# NintendoNinjaSchematic.net
KiCad netlist of a schematic drawn in EAGLE
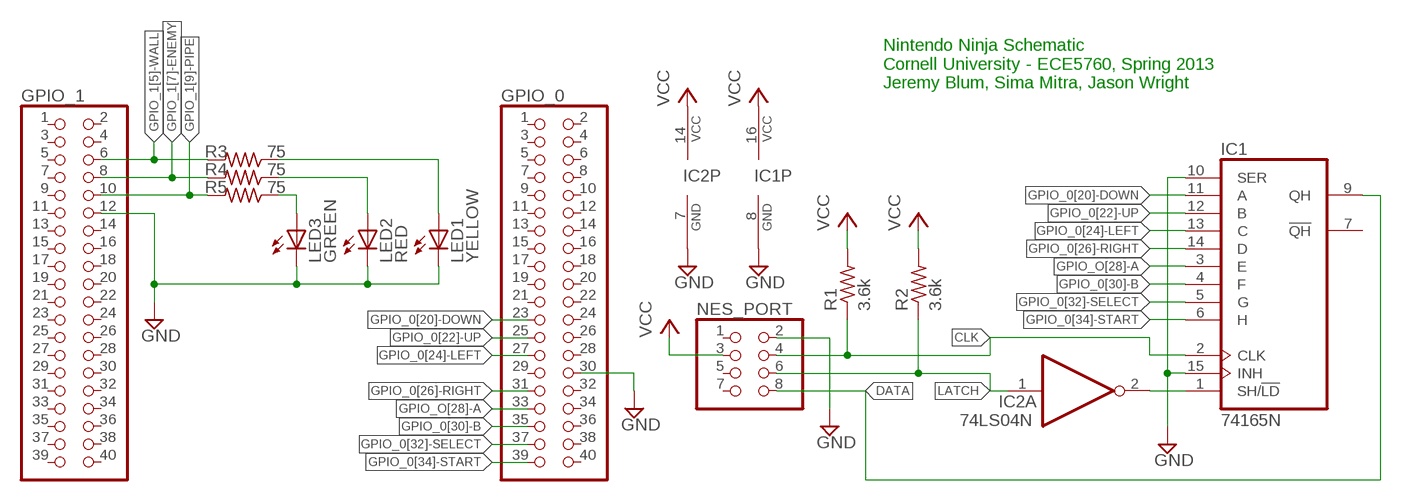
[diagram p0: schematic, sheet 1]

(export (version "E")
  (design (tool "Eeschema 10.0.6"))
  (components
    (comp (ref "GPIO_0")
      (value "PINHD-2X20")
      (footprint "eagle-import:2X20")
      (libsource (lib "eagle-import") (part "PINHD-2X20"))
    )
    (comp (ref "GPIO_1")
      (value "PINHD-2X20")
      (footprint "eagle-import:2X20")
      (libsource (lib "eagle-import") (part "PINHD-2X20"))
    )
    (comp (ref "IC1")
      (value "74165N")
      (footprint "eagle-import:DIL16")
      (libsource (lib "eagle-import") (part "74165N"))
    )
    (comp (ref "IC2")
      (value "74LS04N")
      (footprint "eagle-import:DIL14")
      (libsource (lib "eagle-import") (part "7404NLS"))
    )
    (comp (ref "LED1")
      (value "YELLOW")
      (footprint "eagle-import:LED5MM")
      (libsource (lib "eagle-import") (part "LED5MM"))
    )
    (comp (ref "LED2")
      (value "RED")
      (footprint "eagle-import:LED5MM")
      (libsource (lib "eagle-import") (part "LED5MM"))
    )
    (comp (ref "LED3")
      (value "GREEN")
      (footprint "eagle-import:LED5MM")
      (libsource (lib "eagle-import") (part "LED5MM"))
    )
    (comp (ref "NES_PORT")
      (value "PINHD-2X4")
      (footprint "eagle-import:2X04")
      (libsource (lib "eagle-import") (part "PINHD-2X4"))
    )
    (comp (ref "R1")
      (value "3.6k")
      (footprint "eagle-import:V526-0")
      (libsource (lib "eagle-import") (part "R-US_V526-0"))
    )
    (comp (ref "R2")
      (value "3.6k")
      (footprint "eagle-import:V526-0")
      (libsource (lib "eagle-import") (part "R-US_V526-0"))
    )
    (comp (ref "R3")
      (value "75")
      (footprint "eagle-import:V526-0")
      (libsource (lib "eagle-import") (part "R-US_V526-0"))
    )
    (comp (ref "R4")
      (value "75")
      (footprint "eagle-import:V526-0")
      (libsource (lib "eagle-import") (part "R-US_V526-0"))
    )
    (comp (ref "R5")
      (value "75")
      (footprint "eagle-import:V526-0")
      (libsource (lib "eagle-import") (part "R-US_V526-0"))
    )
  )
  (nets
    (net (code "1") (name "CLK") (class "Default")
      (node (ref "IC1") (pin "2") (pinfunction "CLK_2") (pintype "input"))
      (node (ref "NES_PORT") (pin "4") (pinfunction "4_4") (pintype "passive"))
      (node (ref "R1") (pin "1") (pinfunction "1_1") (pintype "passive"))
    )
    (net (code "2") (name "DATA") (class "Default")
      (node (ref "IC1") (pin "9") (pinfunction "QH_9") (pintype "output"))
      (node (ref "NES_PORT") (pin "8") (pinfunction "8_8") (pintype "passive"))
    )
    (net (code "3") (name "GND") (class "Default")
      (node (ref "GPIO_0") (pin "30") (pinfunction "30_30") (pintype "passive"))
      (node (ref "GPIO_1") (pin "12") (pinfunction "12_12") (pintype "passive"))
      (node (ref "IC1") (pin "10") (pinfunction "SER_10") (pintype "input"))
      (node (ref "IC1") (pin "15") (pinfunction "INH_15") (pintype "input"))
      (node (ref "IC1") (pin "8") (pinfunction "GND_8") (pintype "power_in"))
      (node (ref "IC2") (pin "7") (pinfunction "GND_7") (pintype "power_in"))
      (node (ref "LED1") (pin "K") (pinfunction "C_K") (pintype "passive"))
      (node (ref "LED2") (pin "K") (pinfunction "C_K") (pintype "passive"))
      (node (ref "LED3") (pin "K") (pinfunction "C_K") (pintype "passive"))
      (node (ref "NES_PORT") (pin "2") (pinfunction "2_2") (pintype "passive"))
    )
    (net (code "4") (name "GPIO_0[20]-DOWN") (class "Default")
      (node (ref "GPIO_0") (pin "23") (pinfunction "23_23") (pintype "passive"))
      (node (ref "IC1") (pin "11") (pinfunction "A_11") (pintype "input"))
    )
    (net (code "5") (name "GPIO_0[22]-UP") (class "Default")
      (node (ref "GPIO_0") (pin "25") (pinfunction "25_25") (pintype "passive"))
      (node (ref "IC1") (pin "12") (pinfunction "B_12") (pintype "input"))
    )
    (net (code "6") (name "GPIO_0[24]-LEFT") (class "Default")
      (node (ref "GPIO_0") (pin "27") (pinfunction "27_27") (pintype "passive"))
      (node (ref "IC1") (pin "13") (pinfunction "C_13") (pintype "input"))
    )
    (net (code "7") (name "GPIO_0[26]-RIGHT") (class "Default")
      (node (ref "GPIO_0") (pin "31") (pinfunction "31_31") (pintype "passive"))
      (node (ref "IC1") (pin "14") (pinfunction "D_14") (pintype "input"))
    )
    (net (code "8") (name "GPIO_0[30]-B") (class "Default")
      (node (ref "GPIO_0") (pin "35") (pinfunction "35_35") (pintype "passive"))
      (node (ref "IC1") (pin "4") (pinfunction "F_4") (pintype "input"))
    )
    (net (code "9") (name "GPIO_0[32]-SELECT") (class "Default")
      (node (ref "GPIO_0") (pin "37") (pinfunction "37_37") (pintype "passive"))
      (node (ref "IC1") (pin "5") (pinfunction "G_5") (pintype "input"))
    )
    (net (code "10") (name "GPIO_0[34]-START") (class "Default")
      (node (ref "GPIO_0") (pin "39") (pinfunction "39_39") (pintype "passive"))
      (node (ref "IC1") (pin "6") (pinfunction "H_6") (pintype "input"))
    )
    (net (code "11") (name "GPIO_1[5]-WALL") (class "Default")
      (node (ref "GPIO_1") (pin "6") (pinfunction "6_6") (pintype "passive"))
      (node (ref "R3") (pin "2") (pinfunction "2_2") (pintype "passive"))
    )
    (net (code "12") (name "GPIO_1[7]-ENEMY") (class "Default")
      (node (ref "GPIO_1") (pin "8") (pinfunction "8_8") (pintype "passive"))
      (node (ref "R4") (pin "2") (pinfunction "2_2") (pintype "passive"))
    )
    (net (code "13") (name "GPIO_1[9]-PIPE") (class "Default")
      (node (ref "GPIO_1") (pin "10") (pinfunction "10_10") (pintype "passive"))
      (node (ref "R5") (pin "2") (pinfunction "2_2") (pintype "passive"))
    )
    (net (code "14") (name "GPIO_O[28]-A") (class "Default")
      (node (ref "GPIO_0") (pin "33") (pinfunction "33_33") (pintype "passive"))
      (node (ref "IC1") (pin "3") (pinfunction "E_3") (pintype "input"))
    )
    (net (code "15") (name "LATCH") (class "Default")
      (node (ref "IC2") (pin "1") (pinfunction "I_1") (pintype "input"))
      (node (ref "NES_PORT") (pin "6") (pinfunction "6_6") (pintype "passive"))
      (node (ref "R2") (pin "1") (pinfunction "1_1") (pintype "passive"))
    )
    (net (code "16") (name "Net-(IC1A-SH{slash}~{LD})") (class "Default")
      (node (ref "IC1") (pin "1") (pinfunction "SH/~{LD}_1") (pintype "input"))
      (node (ref "IC2") (pin "2") (pinfunction "O_2") (pintype "output"))
    )
    (net (code "17") (name "Net-(LED1-PadA)") (class "Default")
      (node (ref "LED1") (pin "A") (pinfunction "A_A") (pintype "passive"))
      (node (ref "R3") (pin "1") (pinfunction "1_1") (pintype "passive"))
    )
    (net (code "18") (name "Net-(LED2-PadA)") (class "Default")
      (node (ref "LED2") (pin "A") (pinfunction "A_A") (pintype "passive"))
      (node (ref "R4") (pin "1") (pinfunction "1_1") (pintype "passive"))
    )
    (net (code "19") (name "Net-(LED3-PadA)") (class "Default")
      (node (ref "LED3") (pin "A") (pinfunction "A_A") (pintype "passive"))
      (node (ref "R5") (pin "1") (pinfunction "1_1") (pintype "passive"))
    )
    (net (code "20") (name "VCC") (class "Default")
      (node (ref "IC1") (pin "16") (pinfunction "VCC_16") (pintype "power_in"))
      (node (ref "IC2") (pin "14") (pinfunction "VCC_14") (pintype "power_in"))
      (node (ref "NES_PORT") (pin "3") (pinfunction "3_3") (pintype "passive"))
      (node (ref "R1") (pin "2") (pinfunction "2_2") (pintype "passive"))
      (node (ref "R2") (pin "2") (pinfunction "2_2") (pintype "passive"))
    )
    (net (code "21") (name "unconnected-(GPIO_0-Pad1)") (class "Default")
      (node (ref "GPIO_0") (pin "1") (pinfunction "1_1") (pintype "passive"))
    )
    (net (code "22") (name "unconnected-(GPIO_0-Pad2)") (class "Default")
      (node (ref "GPIO_0") (pin "2") (pinfunction "2_2") (pintype "passive"))
    )
    (net (code "23") (name "unconnected-(GPIO_0-Pad3)") (class "Default")
      (node (ref "GPIO_0") (pin "3") (pinfunction "3_3") (pintype "passive"))
    )
    (net (code "24") (name "unconnected-(GPIO_0-Pad4)") (class "Default")
      (node (ref "GPIO_0") (pin "4") (pinfunction "4_4") (pintype "passive"))
    )
    (net (code "25") (name "unconnected-(GPIO_0-Pad5)") (class "Default")
      (node (ref "GPIO_0") (pin "5") (pinfunction "5_5") (pintype "passive"))
    )
    (net (code "26") (name "unconnected-(GPIO_0-Pad6)") (class "Default")
      (node (ref "GPIO_0") (pin "6") (pinfunction "6_6") (pintype "passive"))
    )
    (net (code "27") (name "unconnected-(GPIO_0-Pad7)") (class "Default")
      (node (ref "GPIO_0") (pin "7") (pinfunction "7_7") (pintype "passive"))
    )
    (net (code "28") (name "unconnected-(GPIO_0-Pad8)") (class "Default")
      (node (ref "GPIO_0") (pin "8") (pinfunction "8_8") (pintype "passive"))
    )
    (net (code "29") (name "unconnected-(GPIO_0-Pad9)") (class "Default")
      (node (ref "GPIO_0") (pin "9") (pinfunction "9_9") (pintype "passive"))
    )
    (net (code "30") (name "unconnected-(GPIO_0-Pad10)") (class "Default")
      (node (ref "GPIO_0") (pin "10") (pinfunction "10_10") (pintype "passive"))
    )
    (net (code "31") (name "unconnected-(GPIO_0-Pad11)") (class "Default")
      (node (ref "GPIO_0") (pin "11") (pinfunction "11_11") (pintype "passive"))
    )
    (net (code "32") (name "unconnected-(GPIO_0-Pad12)") (class "Default")
      (node (ref "GPIO_0") (pin "12") (pinfunction "12_12") (pintype "passive"))
    )
    (net (code "33") (name "unconnected-(GPIO_0-Pad13)") (class "Default")
      (node (ref "GPIO_0") (pin "13") (pinfunction "13_13") (pintype "passive"))
    )
    (net (code "34") (name "unconnected-(GPIO_0-Pad14)") (class "Default")
      (node (ref "GPIO_0") (pin "14") (pinfunction "14_14") (pintype "passive"))
    )
    (net (code "35") (name "unconnected-(GPIO_0-Pad15)") (class "Default")
      (node (ref "GPIO_0") (pin "15") (pinfunction "15_15") (pintype "passive"))
    )
    (net (code "36") (name "unconnected-(GPIO_0-Pad16)") (class "Default")
      (node (ref "GPIO_0") (pin "16") (pinfunction "16_16") (pintype "passive"))
    )
    (net (code "37") (name "unconnected-(GPIO_0-Pad17)") (class "Default")
      (node (ref "GPIO_0") (pin "17") (pinfunction "17_17") (pintype "passive"))
    )
    (net (code "38") (name "unconnected-(GPIO_0-Pad18)") (class "Default")
      (node (ref "GPIO_0") (pin "18") (pinfunction "18_18") (pintype "passive"))
    )
    (net (code "39") (name "unconnected-(GPIO_0-Pad19)") (class "Default")
      (node (ref "GPIO_0") (pin "19") (pinfunction "19_19") (pintype "passive"))
    )
    (net (code "40") (name "unconnected-(GPIO_0-Pad20)") (class "Default")
      (node (ref "GPIO_0") (pin "20") (pinfunction "20_20") (pintype "passive"))
    )
    (net (code "41") (name "unconnected-(GPIO_0-Pad21)") (class "Default")
      (node (ref "GPIO_0") (pin "21") (pinfunction "21_21") (pintype "passive"))
    )
    (net (code "42") (name "unconnected-(GPIO_0-Pad22)") (class "Default")
      (node (ref "GPIO_0") (pin "22") (pinfunction "22_22") (pintype "passive"))
    )
    (net (code "43") (name "unconnected-(GPIO_0-Pad24)") (class "Default")
      (node (ref "GPIO_0") (pin "24") (pinfunction "24_24") (pintype "passive"))
    )
    (net (code "44") (name "unconnected-(GPIO_0-Pad26)") (class "Default")
      (node (ref "GPIO_0") (pin "26") (pinfunction "26_26") (pintype "passive"))
    )
    (net (code "45") (name "unconnected-(GPIO_0-Pad28)") (class "Default")
      (node (ref "GPIO_0") (pin "28") (pinfunction "28_28") (pintype "passive"))
    )
    (net (code "46") (name "unconnected-(GPIO_0-Pad29)") (class "Default")
      (node (ref "GPIO_0") (pin "29") (pinfunction "29_29") (pintype "passive"))
    )
    (net (code "47") (name "unconnected-(GPIO_0-Pad32)") (class "Default")
      (node (ref "GPIO_0") (pin "32") (pinfunction "32_32") (pintype "passive"))
    )
    (net (code "48") (name "unconnected-(GPIO_0-Pad34)") (class "Default")
      (node (ref "GPIO_0") (pin "34") (pinfunction "34_34") (pintype "passive"))
    )
    (net (code "49") (name "unconnected-(GPIO_0-Pad36)") (class "Default")
      (node (ref "GPIO_0") (pin "36") (pinfunction "36_36") (pintype "passive"))
    )
    (net (code "50") (name "unconnected-(GPIO_0-Pad38)") (class "Default")
      (node (ref "GPIO_0") (pin "38") (pinfunction "38_38") (pintype "passive"))
    )
    (net (code "51") (name "unconnected-(GPIO_0-Pad40)") (class "Default")
      (node (ref "GPIO_0") (pin "40") (pinfunction "40_40") (pintype "passive"))
    )
    (net (code "52") (name "unconnected-(GPIO_1-Pad1)") (class "Default")
      (node (ref "GPIO_1") (pin "1") (pinfunction "1_1") (pintype "passive"))
    )
    (net (code "53") (name "unconnected-(GPIO_1-Pad2)") (class "Default")
      (node (ref "GPIO_1") (pin "2") (pinfunction "2_2") (pintype "passive"))
    )
    (net (code "54") (name "unconnected-(GPIO_1-Pad3)") (class "Default")
      (node (ref "GPIO_1") (pin "3") (pinfunction "3_3") (pintype "passive"))
    )
    (net (code "55") (name "unconnected-(GPIO_1-Pad4)") (class "Default")
      (node (ref "GPIO_1") (pin "4") (pinfunction "4_4") (pintype "passive"))
    )
    (net (code "56") (name "unconnected-(GPIO_1-Pad5)") (class "Default")
      (node (ref "GPIO_1") (pin "5") (pinfunction "5_5") (pintype "passive"))
    )
    (net (code "57") (name "unconnected-(GPIO_1-Pad7)") (class "Default")
      (node (ref "GPIO_1") (pin "7") (pinfunction "7_7") (pintype "passive"))
    )
    (net (code "58") (name "unconnected-(GPIO_1-Pad9)") (class "Default")
      (node (ref "GPIO_1") (pin "9") (pinfunction "9_9") (pintype "passive"))
    )
    (net (code "59") (name "unconnected-(GPIO_1-Pad11)") (class "Default")
      (node (ref "GPIO_1") (pin "11") (pinfunction "11_11") (pintype "passive"))
    )
    (net (code "60") (name "unconnected-(GPIO_1-Pad13)") (class "Default")
      (node (ref "GPIO_1") (pin "13") (pinfunction "13_13") (pintype "passive"))
    )
    (net (code "61") (name "unconnected-(GPIO_1-Pad14)") (class "Default")
      (node (ref "GPIO_1") (pin "14") (pinfunction "14_14") (pintype "passive"))
    )
    (net (code "62") (name "unconnected-(GPIO_1-Pad15)") (class "Default")
      (node (ref "GPIO_1") (pin "15") (pinfunction "15_15") (pintype "passive"))
    )
    (net (code "63") (name "unconnected-(GPIO_1-Pad16)") (class "Default")
      (node (ref "GPIO_1") (pin "16") (pinfunction "16_16") (pintype "passive"))
    )
    (net (code "64") (name "unconnected-(GPIO_1-Pad17)") (class "Default")
      (node (ref "GPIO_1") (pin "17") (pinfunction "17_17") (pintype "passive"))
    )
    (net (code "65") (name "unconnected-(GPIO_1-Pad18)") (class "Default")
      (node (ref "GPIO_1") (pin "18") (pinfunction "18_18") (pintype "passive"))
    )
    (net (code "66") (name "unconnected-(GPIO_1-Pad19)") (class "Default")
      (node (ref "GPIO_1") (pin "19") (pinfunction "19_19") (pintype "passive"))
    )
    (net (code "67") (name "unconnected-(GPIO_1-Pad20)") (class "Default")
      (node (ref "GPIO_1") (pin "20") (pinfunction "20_20") (pintype "passive"))
    )
    (net (code "68") (name "unconnected-(GPIO_1-Pad21)") (class "Default")
      (node (ref "GPIO_1") (pin "21") (pinfunction "21_21") (pintype "passive"))
    )
    (net (code "69") (name "unconnected-(GPIO_1-Pad22)") (class "Default")
      (node (ref "GPIO_1") (pin "22") (pinfunction "22_22") (pintype "passive"))
    )
    (net (code "70") (name "unconnected-(GPIO_1-Pad23)") (class "Default")
      (node (ref "GPIO_1") (pin "23") (pinfunction "23_23") (pintype "passive"))
    )
    (net (code "71") (name "unconnected-(GPIO_1-Pad24)") (class "Default")
      (node (ref "GPIO_1") (pin "24") (pinfunction "24_24") (pintype "passive"))
    )
    (net (code "72") (name "unconnected-(GPIO_1-Pad25)") (class "Default")
      (node (ref "GPIO_1") (pin "25") (pinfunction "25_25") (pintype "passive"))
    )
    (net (code "73") (name "unconnected-(GPIO_1-Pad26)") (class "Default")
      (node (ref "GPIO_1") (pin "26") (pinfunction "26_26") (pintype "passive"))
    )
    (net (code "74") (name "unconnected-(GPIO_1-Pad27)") (class "Default")
      (node (ref "GPIO_1") (pin "27") (pinfunction "27_27") (pintype "passive"))
    )
    (net (code "75") (name "unconnected-(GPIO_1-Pad28)") (class "Default")
      (node (ref "GPIO_1") (pin "28") (pinfunction "28_28") (pintype "passive"))
    )
    (net (code "76") (name "unconnected-(GPIO_1-Pad29)") (class "Default")
      (node (ref "GPIO_1") (pin "29") (pinfunction "29_29") (pintype "passive"))
    )
    (net (code "77") (name "unconnected-(GPIO_1-Pad30)") (class "Default")
      (node (ref "GPIO_1") (pin "30") (pinfunction "30_30") (pintype "passive"))
    )
    (net (code "78") (name "unconnected-(GPIO_1-Pad31)") (class "Default")
      (node (ref "GPIO_1") (pin "31") (pinfunction "31_31") (pintype "passive"))
    )
    (net (code "79") (name "unconnected-(GPIO_1-Pad32)") (class "Default")
      (node (ref "GPIO_1") (pin "32") (pinfunction "32_32") (pintype "passive"))
    )
    (net (code "80") (name "unconnected-(GPIO_1-Pad33)") (class "Default")
      (node (ref "GPIO_1") (pin "33") (pinfunction "33_33") (pintype "passive"))
    )
    (net (code "81") (name "unconnected-(GPIO_1-Pad34)") (class "Default")
      (node (ref "GPIO_1") (pin "34") (pinfunction "34_34") (pintype "passive"))
    )
    (net (code "82") (name "unconnected-(GPIO_1-Pad35)") (class "Default")
      (node (ref "GPIO_1") (pin "35") (pinfunction "35_35") (pintype "passive"))
    )
    (net (code "83") (name "unconnected-(GPIO_1-Pad36)") (class "Default")
      (node (ref "GPIO_1") (pin "36") (pinfunction "36_36") (pintype "passive"))
    )
    (net (code "84") (name "unconnected-(GPIO_1-Pad37)") (class "Default")
      (node (ref "GPIO_1") (pin "37") (pinfunction "37_37") (pintype "passive"))
    )
    (net (code "85") (name "unconnected-(GPIO_1-Pad38)") (class "Default")
      (node (ref "GPIO_1") (pin "38") (pinfunction "38_38") (pintype "passive"))
    )
    (net (code "86") (name "unconnected-(GPIO_1-Pad39)") (class "Default")
      (node (ref "GPIO_1") (pin "39") (pinfunction "39_39") (pintype "passive"))
    )
    (net (code "87") (name "unconnected-(GPIO_1-Pad40)") (class "Default")
      (node (ref "GPIO_1") (pin "40") (pinfunction "40_40") (pintype "passive"))
    )
    (net (code "88") (name "unconnected-(IC1A-~{QH}-Pad7)") (class "Default")
      (node (ref "IC1") (pin "7") (pinfunction "~{QH}_7") (pintype "output"))
    )
    (net (code "89") (name "unconnected-(NES_PORT-Pad1)") (class "Default")
      (node (ref "NES_PORT") (pin "1") (pinfunction "1_1") (pintype "passive"))
    )
    (net (code "90") (name "unconnected-(NES_PORT-Pad5)") (class "Default")
      (node (ref "NES_PORT") (pin "5") (pinfunction "5_5") (pintype "passive"))
    )
    (net (code "91") (name "unconnected-(NES_PORT-Pad7)") (class "Default")
      (node (ref "NES_PORT") (pin "7") (pinfunction "7_7") (pintype "passive"))
    )
  )
)
